# ID_MEMORY.net
KiCad netlist of a schematic drawn in Altium Designer
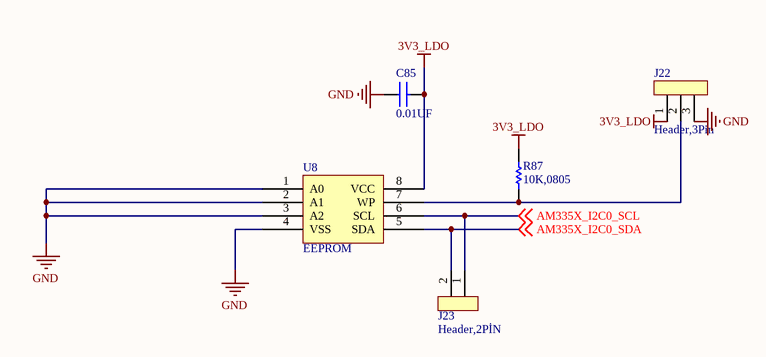
[diagram p0: ID_MEMORY.SchDoc]

(export (version "E")
  (design (tool "Eeschema 10.0.6"))
  (components
    (comp (ref "C85")
      (value "0.01UF")
      (footprint "0805")
      (description "MULTICOMP - MCSH21B103K100CT - CAP, MLCC, X7R, 10NF, 10V, 0805")
      (fields
        (field (name "MANUFACTURER") "MULTICOMP")
        (field (name "MANUFACTURER PART NUMBER") "MCSH21B103K100CT")
      )
      (libsource (lib "LINUX") (part "0.01UF"))
    )
    (comp (ref "J22")
      (value "Header,3Pin")
      (footprint "HEADER,3PİN")
      (libsource (lib "LINUX") (part "Header,3Pin"))
    )
    (comp (ref "J23")
      (value "Header,2PİN")
      (footprint "HEADER,2PİN")
      (libsource (lib "LINUX") (part "Header,2PİN"))
    )
    (comp (ref "R87")
      (value "10K,0805")
      (footprint "0805")
      (description "BOURNS - CR0805-FX-1002GLF - RESISTOR, 10K, 0.125W, 1%")
      (fields
        (field (name "MANUFACTURER") "BOURNS")
        (field (name "MANUFACTURER PART NUMBER") "CR0805-FX-1002GLF")
      )
      (libsource (lib "LINUX") (part "10K,0805"))
    )
    (comp (ref "U8")
      (value "EEPROM")
      (footprint "SOIC-8")
      (fields
        (field (name "MANUFACTURER") "ON Semiconductor")
        (field (name "MANUFACTURER PART NUMBER") "CAT24C256WI-GT3")
      )
      (libsource (lib "LINUX") (part "EEPROM"))
    )
  )
  (nets
    (net (code "1") (name "3V3_LDO") (class "Default")
      (node (ref "C85") (pin "2") (pinfunction "2_2") (pintype "passive"))
      (node (ref "J22") (pin "1") (pinfunction "1_1") (pintype "passive"))
      (node (ref "R87") (pin "2") (pinfunction "2_2") (pintype "passive"))
      (node (ref "U8") (pin "8") (pinfunction "VCC_8") (pintype "passive"))
    )
    (net (code "2") (name "AM335X_I2C0_SCL") (class "Default")
      (node (ref "J23") (pin "1") (pinfunction "1_1") (pintype "passive"))
      (node (ref "U8") (pin "6") (pinfunction "SCL_6") (pintype "passive"))
    )
    (net (code "3") (name "AM335X_I2C0_SDA") (class "Default")
      (node (ref "J23") (pin "2") (pinfunction "2_2") (pintype "passive"))
      (node (ref "U8") (pin "5") (pinfunction "SDA_5") (pintype "passive"))
    )
    (net (code "4") (name "GND") (class "Default")
      (node (ref "C85") (pin "1") (pinfunction "1_1") (pintype "passive"))
      (node (ref "J22") (pin "3") (pinfunction "3_3") (pintype "passive"))
      (node (ref "U8") (pin "1") (pinfunction "A0_1") (pintype "passive"))
      (node (ref "U8") (pin "2") (pinfunction "A1_2") (pintype "passive"))
      (node (ref "U8") (pin "3") (pinfunction "A2_3") (pintype "passive"))
      (node (ref "U8") (pin "4") (pinfunction "VSS_4") (pintype "passive"))
    )
    (net (code "5") (name "Net-(U8-WP)") (class "Default")
      (node (ref "J22") (pin "2") (pinfunction "2_2") (pintype "passive"))
      (node (ref "R87") (pin "1") (pinfunction "1_1") (pintype "passive"))
      (node (ref "U8") (pin "7") (pinfunction "WP_7") (pintype "passive"))
    )
  )
)
